# mp28164-buck-boost-flashlight-driver-tes.net
KiCad netlist of a schematic drawn in EAGLE
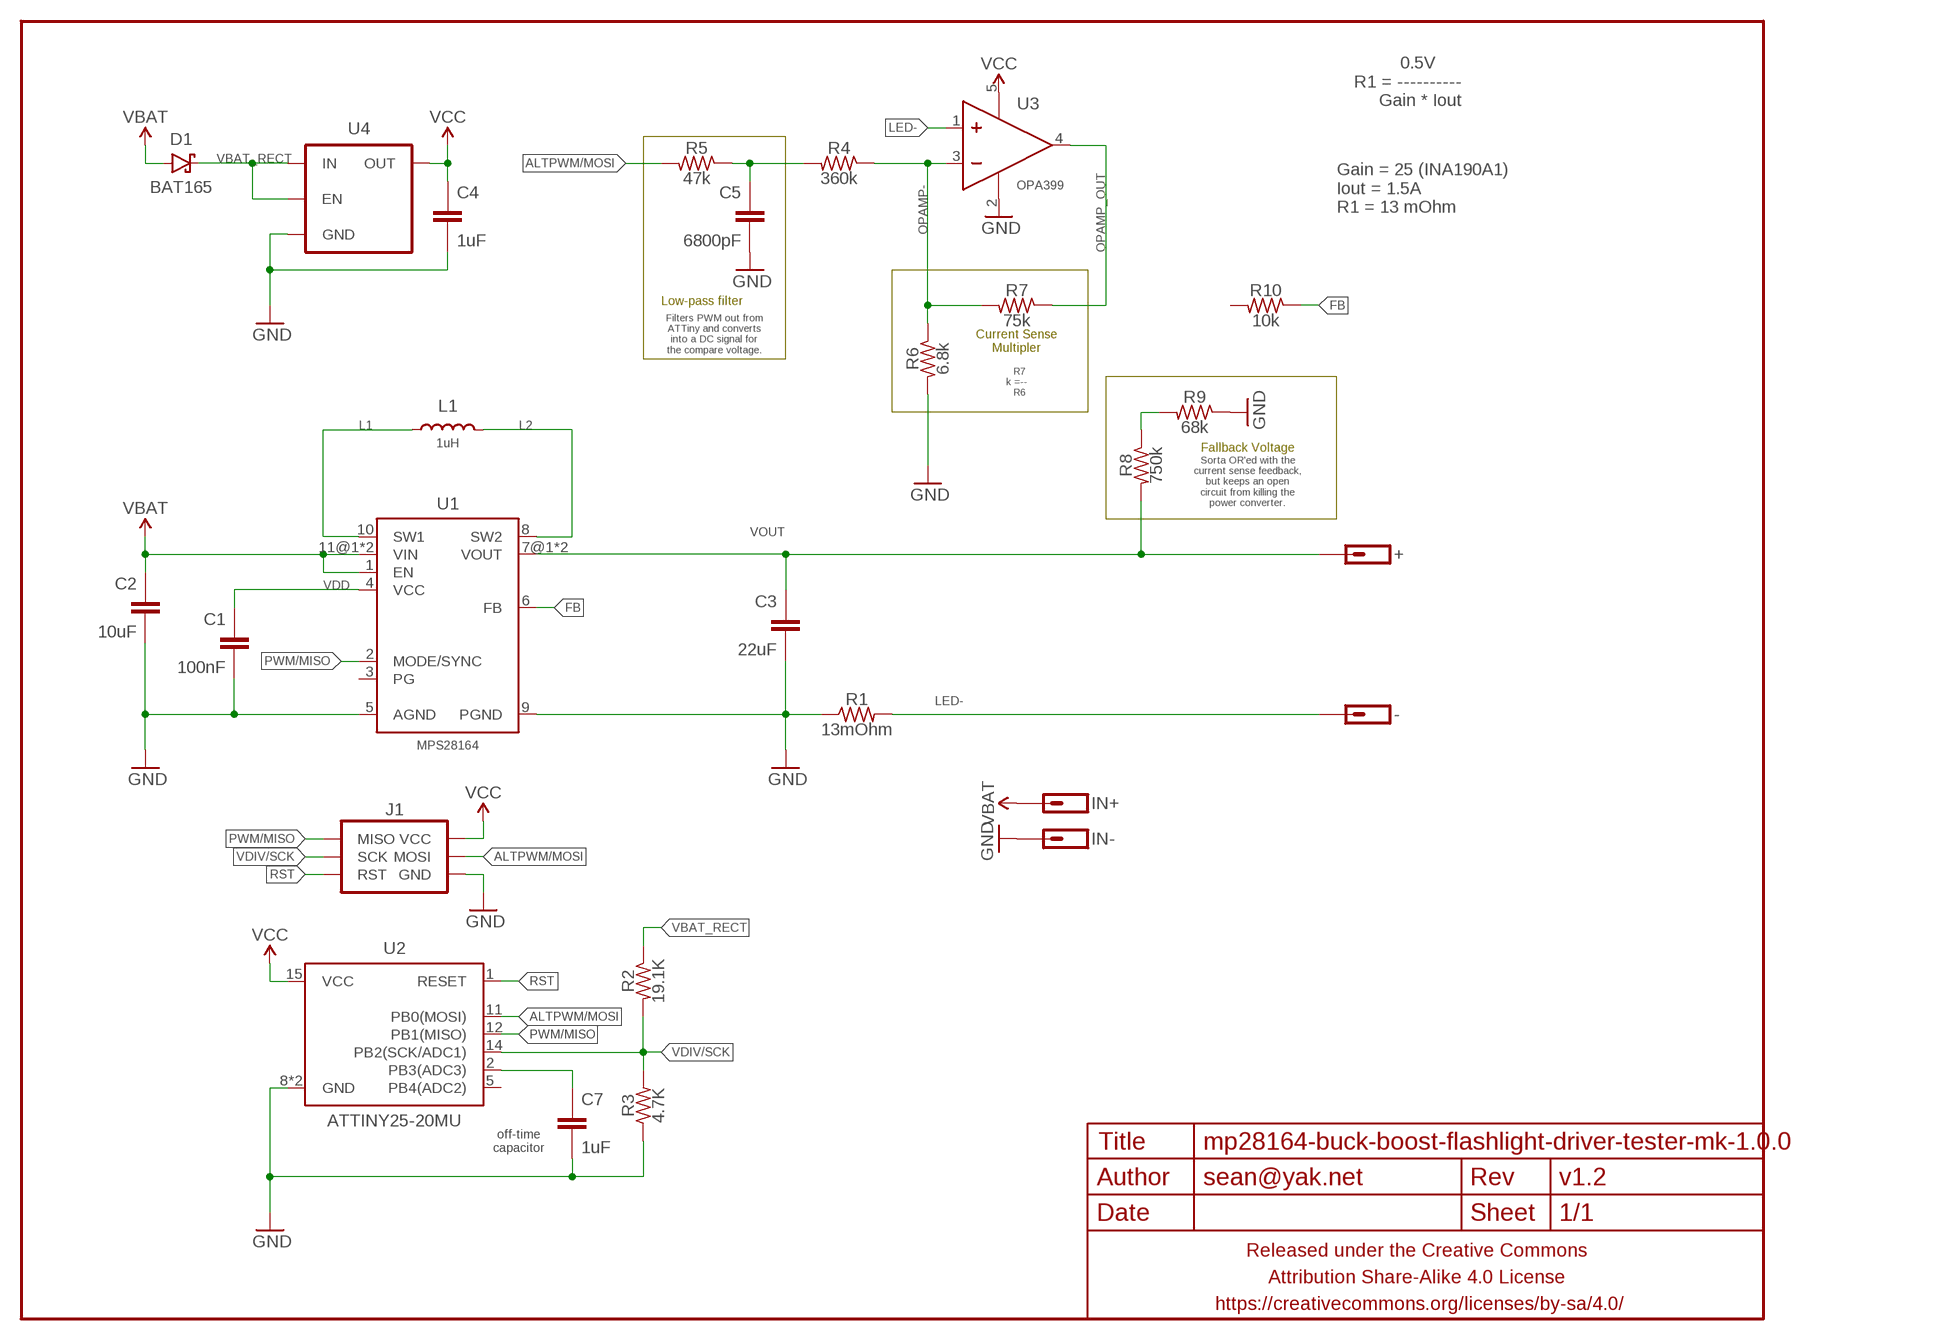
[diagram p0: schematic, sheet 1]

(export (version "E")
  (design (tool "Eeschema 10.0.6"))
  (components
    (comp (ref "+")
      (value "M01PTH-1MM-CIR-NS")
      (footprint "eagle-import:1X01-1MM-CIR-NS")
      (libsource (lib "eagle-import") (part "M01PTH-1MM-CIR-NS"))
    )
    (comp (ref "-")
      (value "M01PTH-1MM-CIR-NS")
      (footprint "eagle-import:1X01-1MM-CIR-NS")
      (libsource (lib "eagle-import") (part "M01PTH-1MM-CIR-NS"))
    )
    (comp (ref "C1")
      (value "100nF")
      (footprint "eagle-import:C0402")
      (libsource (lib "eagle-import") (part "CAPACITOR-CERAMICC0402"))
    )
    (comp (ref "C2")
      (value "10uF")
      (footprint "eagle-import:C0805-TIGHTER")
      (libsource (lib "eagle-import") (part "CAPACITOR-CERAMICC0805-TIGHTER"))
    )
    (comp (ref "C3")
      (value "22uF")
      (footprint "eagle-import:C0805-TIGHTER")
      (libsource (lib "eagle-import") (part "CAPACITOR-CERAMICC0805-TIGHTER"))
    )
    (comp (ref "C4")
      (value "1uF")
      (footprint "eagle-import:C0402")
      (libsource (lib "eagle-import") (part "CAPACITOR-CERAMICC0402"))
    )
    (comp (ref "C5")
      (value "6800pF")
      (footprint "eagle-import:C0402")
      (libsource (lib "eagle-import") (part "CAPACITOR-CERAMICC0402"))
    )
    (comp (ref "C7")
      (value "1uF")
      (footprint "eagle-import:C0402")
      (libsource (lib "eagle-import") (part "CAPACITOR-CERAMICC0402"))
    )
    (comp (ref "D1")
      (value "BAT165")
      (footprint "eagle-import:SOD323-SCHOTTKY")
      (libsource (lib "eagle-import") (part "DIODE-SCHOTTKYSOD323"))
    )
    (comp (ref "FRAME1")
      (value "FRAME-LETTERNO_PACKAGE")
      (footprint "eagle-import:DUMMY")
      (fields
        (field (name "DESIGNER") "sean@yak.net")
        (field (name "VERSION") "v1.2")
        (field (name "DESIGNER_1") "sean@yak.net")
        (field (name "VERSION_1") "v1.2")
      )
      (libsource (lib "eagle-import") (part "FRAME-LETTERNO_PACKAGE"))
    )
    (comp (ref "IN+")
      (value "M01PTH-1MM-CIR-NS")
      (footprint "eagle-import:1X01-1MM-CIR-NS")
      (libsource (lib "eagle-import") (part "M01PTH-1MM-CIR-NS"))
    )
    (comp (ref "IN-")
      (value "M01PTH-1MM-CIR-NS")
      (footprint "eagle-import:1X01-1MM-CIR-NS")
      (libsource (lib "eagle-import") (part "M01PTH-1MM-CIR-NS"))
    )
    (comp (ref "J1")
      (value "AVR_SPI_PRG_6SMD-1.27MM")
      (footprint "eagle-import:2X3-1.27MM-SMD")
      (libsource (lib "eagle-import") (part "AVR_SPI_PRG_6SMD-1.27MM"))
    )
    (comp (ref "L1")
      (value "1uH")
      (footprint "eagle-import:XAR7030")
      (libsource (lib "eagle-import") (part "INDUCTORXAR7030"))
    )
    (comp (ref "R1")
      (value "13mOhm")
      (footprint "eagle-import:R0805-TIGHTER")
      (libsource (lib "eagle-import") (part "RESISTORR0805-TIGHTER"))
    )
    (comp (ref "R2")
      (value "19.1K")
      (footprint "eagle-import:R0402")
      (libsource (lib "eagle-import") (part "RESISTORR0402"))
    )
    (comp (ref "R3")
      (value "4.7K")
      (footprint "eagle-import:R0402")
      (libsource (lib "eagle-import") (part "RESISTORR0402"))
    )
    (comp (ref "R4")
      (value "360k")
      (footprint "eagle-import:R0402")
      (libsource (lib "eagle-import") (part "RESISTORR0402"))
    )
    (comp (ref "R5")
      (value "47k")
      (footprint "eagle-import:R0402")
      (libsource (lib "eagle-import") (part "RESISTORR0402"))
    )
    (comp (ref "R6")
      (value "6.8k")
      (footprint "eagle-import:R0402")
      (libsource (lib "eagle-import") (part "RESISTORR0402"))
    )
    (comp (ref "R7")
      (value "75k")
      (footprint "eagle-import:R0402")
      (libsource (lib "eagle-import") (part "RESISTORR0402"))
    )
    (comp (ref "R8")
      (value "750k")
      (footprint "eagle-import:R0402")
      (libsource (lib "eagle-import") (part "RESISTORR0402"))
    )
    (comp (ref "R9")
      (value "68k")
      (footprint "eagle-import:R0402")
      (libsource (lib "eagle-import") (part "RESISTORR0402"))
    )
    (comp (ref "R10")
      (value "10k")
      (footprint "eagle-import:R0402")
      (libsource (lib "eagle-import") (part "RESISTORR0402"))
    )
    (comp (ref "U1")
      (value "MPS28164")
      (footprint "eagle-import:MPS28164")
      (libsource (lib "eagle-import") (part "MPS28164"))
    )
    (comp (ref "U2")
      (value "ATTINY25-20MU")
      (footprint "eagle-import:QFN20")
      (libsource (lib "eagle-import") (part "ATTINY45TINY85-20-QFN"))
    )
    (comp (ref "U3")
      (value "OPA399")
      (footprint "eagle-import:SC70")
      (libsource (lib "eagle-import") (part "OPAMPOPA333-SC-70"))
    )
    (comp (ref "U4")
      (value "V_REG_ENTLV700")
      (footprint "eagle-import:SC70")
      (libsource (lib "eagle-import") (part "V_REG_ENTLV700"))
    )
  )
  (nets
    (net (code "1") (name "/L1") (class "Default")
      (node (ref "L1") (pin "P$1") (pinfunction "1_P$1") (pintype "passive"))
      (node (ref "U1") (pin "10") (pinfunction "SW1_10") (pintype "bidirectional"))
    )
    (net (code "2") (name "/L2") (class "Default")
      (node (ref "L1") (pin "P$2") (pinfunction "2_P$2") (pintype "passive"))
      (node (ref "U1") (pin "8") (pinfunction "SW2_8") (pintype "bidirectional"))
    )
    (net (code "3") (name "/OPAMP-") (class "Default")
      (node (ref "R4") (pin "1") (pinfunction "1_1") (pintype "passive"))
      (node (ref "R6") (pin "1") (pinfunction "1_1") (pintype "passive"))
      (node (ref "R7") (pin "2") (pinfunction "2_2") (pintype "passive"))
      (node (ref "U3") (pin "3") (pinfunction "IN-_3") (pintype "input"))
    )
    (net (code "4") (name "/OPAMP_OUT") (class "Default")
      (node (ref "R7") (pin "1") (pinfunction "1_1") (pintype "passive"))
      (node (ref "U3") (pin "4") (pinfunction "OUT_4") (pintype "output"))
    )
    (net (code "5") (name "/VDD") (class "Default")
      (node (ref "C1") (pin "1") (pinfunction "1_1") (pintype "passive"))
      (node (ref "U1") (pin "4") (pinfunction "VCC_4") (pintype "bidirectional"))
    )
    (net (code "6") (name "/VOUT") (class "Default")
      (node (ref "+") (pin "1") (pinfunction "1_1") (pintype "passive"))
      (node (ref "C3") (pin "1") (pinfunction "1_1") (pintype "passive"))
      (node (ref "R8") (pin "2") (pinfunction "2_2") (pintype "passive"))
      (node (ref "U1") (pin "7@1") (pinfunction "VOUT_7@1") (pintype "bidirectional"))
      (node (ref "U1") (pin "7@2") (pinfunction "VOUT_7@2") (pintype "bidirectional"))
    )
    (net (code "7") (name "ALTPWM{slash}MOSI") (class "Default")
      (node (ref "J1") (pin "4") (pinfunction "MOSI_4") (pintype "passive"))
      (node (ref "R5") (pin "2") (pinfunction "2_2") (pintype "passive"))
      (node (ref "U2") (pin "11") (pinfunction "PB0(MOSI)_11") (pintype "bidirectional"))
    )
    (net (code "8") (name "FB") (class "Default")
      (node (ref "R10") (pin "1") (pinfunction "1_1") (pintype "passive"))
      (node (ref "U1") (pin "6") (pinfunction "FB_6") (pintype "bidirectional"))
    )
    (net (code "9") (name "GND") (class "Default")
      (node (ref "C1") (pin "2") (pinfunction "2_2") (pintype "passive"))
      (node (ref "C2") (pin "2") (pinfunction "2_2") (pintype "passive"))
      (node (ref "C3") (pin "2") (pinfunction "2_2") (pintype "passive"))
      (node (ref "C4") (pin "2") (pinfunction "2_2") (pintype "passive"))
      (node (ref "C5") (pin "2") (pinfunction "2_2") (pintype "passive"))
      (node (ref "C7") (pin "2") (pinfunction "2_2") (pintype "passive"))
      (node (ref "IN-") (pin "1") (pinfunction "1_1") (pintype "passive"))
      (node (ref "J1") (pin "6") (pinfunction "GND_6") (pintype "passive"))
      (node (ref "R1") (pin "1") (pinfunction "1_1") (pintype "passive"))
      (node (ref "R3") (pin "1") (pinfunction "1_1") (pintype "passive"))
      (node (ref "R6") (pin "2") (pinfunction "2_2") (pintype "passive"))
      (node (ref "R9") (pin "1") (pinfunction "1_1") (pintype "passive"))
      (node (ref "U1") (pin "5") (pinfunction "AGND_5") (pintype "bidirectional"))
      (node (ref "U1") (pin "9") (pinfunction "PGND_9") (pintype "bidirectional"))
      (node (ref "U2") (pin "8") (pinfunction "GND_8") (pintype "bidirectional"))
      (node (ref "U2") (pin "PAD") (pinfunction "GND_PAD") (pintype "bidirectional"))
      (node (ref "U3") (pin "2") (pinfunction "V-_2") (pintype "power_in"))
      (node (ref "U4") (pin "2") (pinfunction "GND_2") (pintype "input"))
    )
    (net (code "10") (name "LED-") (class "Default")
      (node (ref "-") (pin "1") (pinfunction "1_1") (pintype "passive"))
      (node (ref "R1") (pin "2") (pinfunction "2_2") (pintype "passive"))
      (node (ref "U3") (pin "1") (pinfunction "IN+_1") (pintype "input"))
    )
    (net (code "11") (name "Net-(C5-Pad1)") (class "Default")
      (node (ref "C5") (pin "1") (pinfunction "1_1") (pintype "passive"))
      (node (ref "R4") (pin "2") (pinfunction "2_2") (pintype "passive"))
      (node (ref "R5") (pin "1") (pinfunction "1_1") (pintype "passive"))
    )
    (net (code "12") (name "Net-(R8-Pad1)") (class "Default")
      (node (ref "R8") (pin "1") (pinfunction "1_1") (pintype "passive"))
      (node (ref "R9") (pin "2") (pinfunction "2_2") (pintype "passive"))
    )
    (net (code "13") (name "Net-(U2-PB3(ADC3))") (class "Default")
      (node (ref "C7") (pin "1") (pinfunction "1_1") (pintype "passive"))
      (node (ref "U2") (pin "2") (pinfunction "PB3(ADC3)_2") (pintype "bidirectional"))
    )
    (net (code "14") (name "PWM{slash}MISO") (class "Default")
      (node (ref "J1") (pin "1") (pinfunction "MISO_1") (pintype "passive"))
      (node (ref "U1") (pin "2") (pinfunction "MODE/SYNC_2") (pintype "bidirectional"))
      (node (ref "U2") (pin "12") (pinfunction "PB1(MISO)_12") (pintype "bidirectional"))
    )
    (net (code "15") (name "RST") (class "Default")
      (node (ref "J1") (pin "5") (pinfunction "RST_5") (pintype "passive"))
      (node (ref "U2") (pin "1") (pinfunction "RESET_1") (pintype "bidirectional"))
    )
    (net (code "16") (name "VBAT") (class "Default")
      (node (ref "C2") (pin "1") (pinfunction "1_1") (pintype "passive"))
      (node (ref "D1") (pin "A") (pinfunction "A_A") (pintype "passive"))
      (node (ref "IN+") (pin "1") (pinfunction "1_1") (pintype "passive"))
      (node (ref "U1") (pin "1") (pinfunction "EN_1") (pintype "bidirectional"))
      (node (ref "U1") (pin "11@1") (pinfunction "VIN_11@1") (pintype "bidirectional"))
      (node (ref "U1") (pin "11@2") (pinfunction "VIN_11@2") (pintype "bidirectional"))
    )
    (net (code "17") (name "VBAT_RECT") (class "Default")
      (node (ref "D1") (pin "C") (pinfunction "C_C") (pintype "passive"))
      (node (ref "R2") (pin "1") (pinfunction "1_1") (pintype "passive"))
      (node (ref "U4") (pin "1") (pinfunction "IN_1") (pintype "input"))
      (node (ref "U4") (pin "3") (pinfunction "EN_3") (pintype "input"))
    )
    (net (code "18") (name "VCC") (class "Default")
      (node (ref "C4") (pin "1") (pinfunction "1_1") (pintype "passive"))
      (node (ref "J1") (pin "2") (pinfunction "VCC_2") (pintype "passive"))
      (node (ref "U2") (pin "15") (pinfunction "VCC_15") (pintype "bidirectional"))
      (node (ref "U3") (pin "5") (pinfunction "V+_5") (pintype "power_in"))
      (node (ref "U4") (pin "5") (pinfunction "OUT_5") (pintype "passive"))
    )
    (net (code "19") (name "VDIV{slash}SCK") (class "Default")
      (node (ref "J1") (pin "3") (pinfunction "SCK_3") (pintype "passive"))
      (node (ref "R2") (pin "2") (pinfunction "2_2") (pintype "passive"))
      (node (ref "R3") (pin "2") (pinfunction "2_2") (pintype "passive"))
      (node (ref "U2") (pin "14") (pinfunction "PB2(SCK/ADC1)_14") (pintype "bidirectional"))
    )
    (net (code "20") (name "unconnected-(R10-Pad2)") (class "Default")
      (node (ref "R10") (pin "2") (pinfunction "2_2") (pintype "passive"))
    )
    (net (code "21") (name "unconnected-(U1-PG-Pad3)") (class "Default")
      (node (ref "U1") (pin "3") (pinfunction "PG_3") (pintype "bidirectional"))
    )
    (net (code "22") (name "unconnected-(U2-PB4(ADC2)-Pad5)") (class "Default")
      (node (ref "U2") (pin "5") (pinfunction "PB4(ADC2)_5") (pintype "bidirectional"))
    )
  )
)
